# CAN-BUS-Shield-v1_2.net
KiCad netlist of a schematic drawn in EAGLE
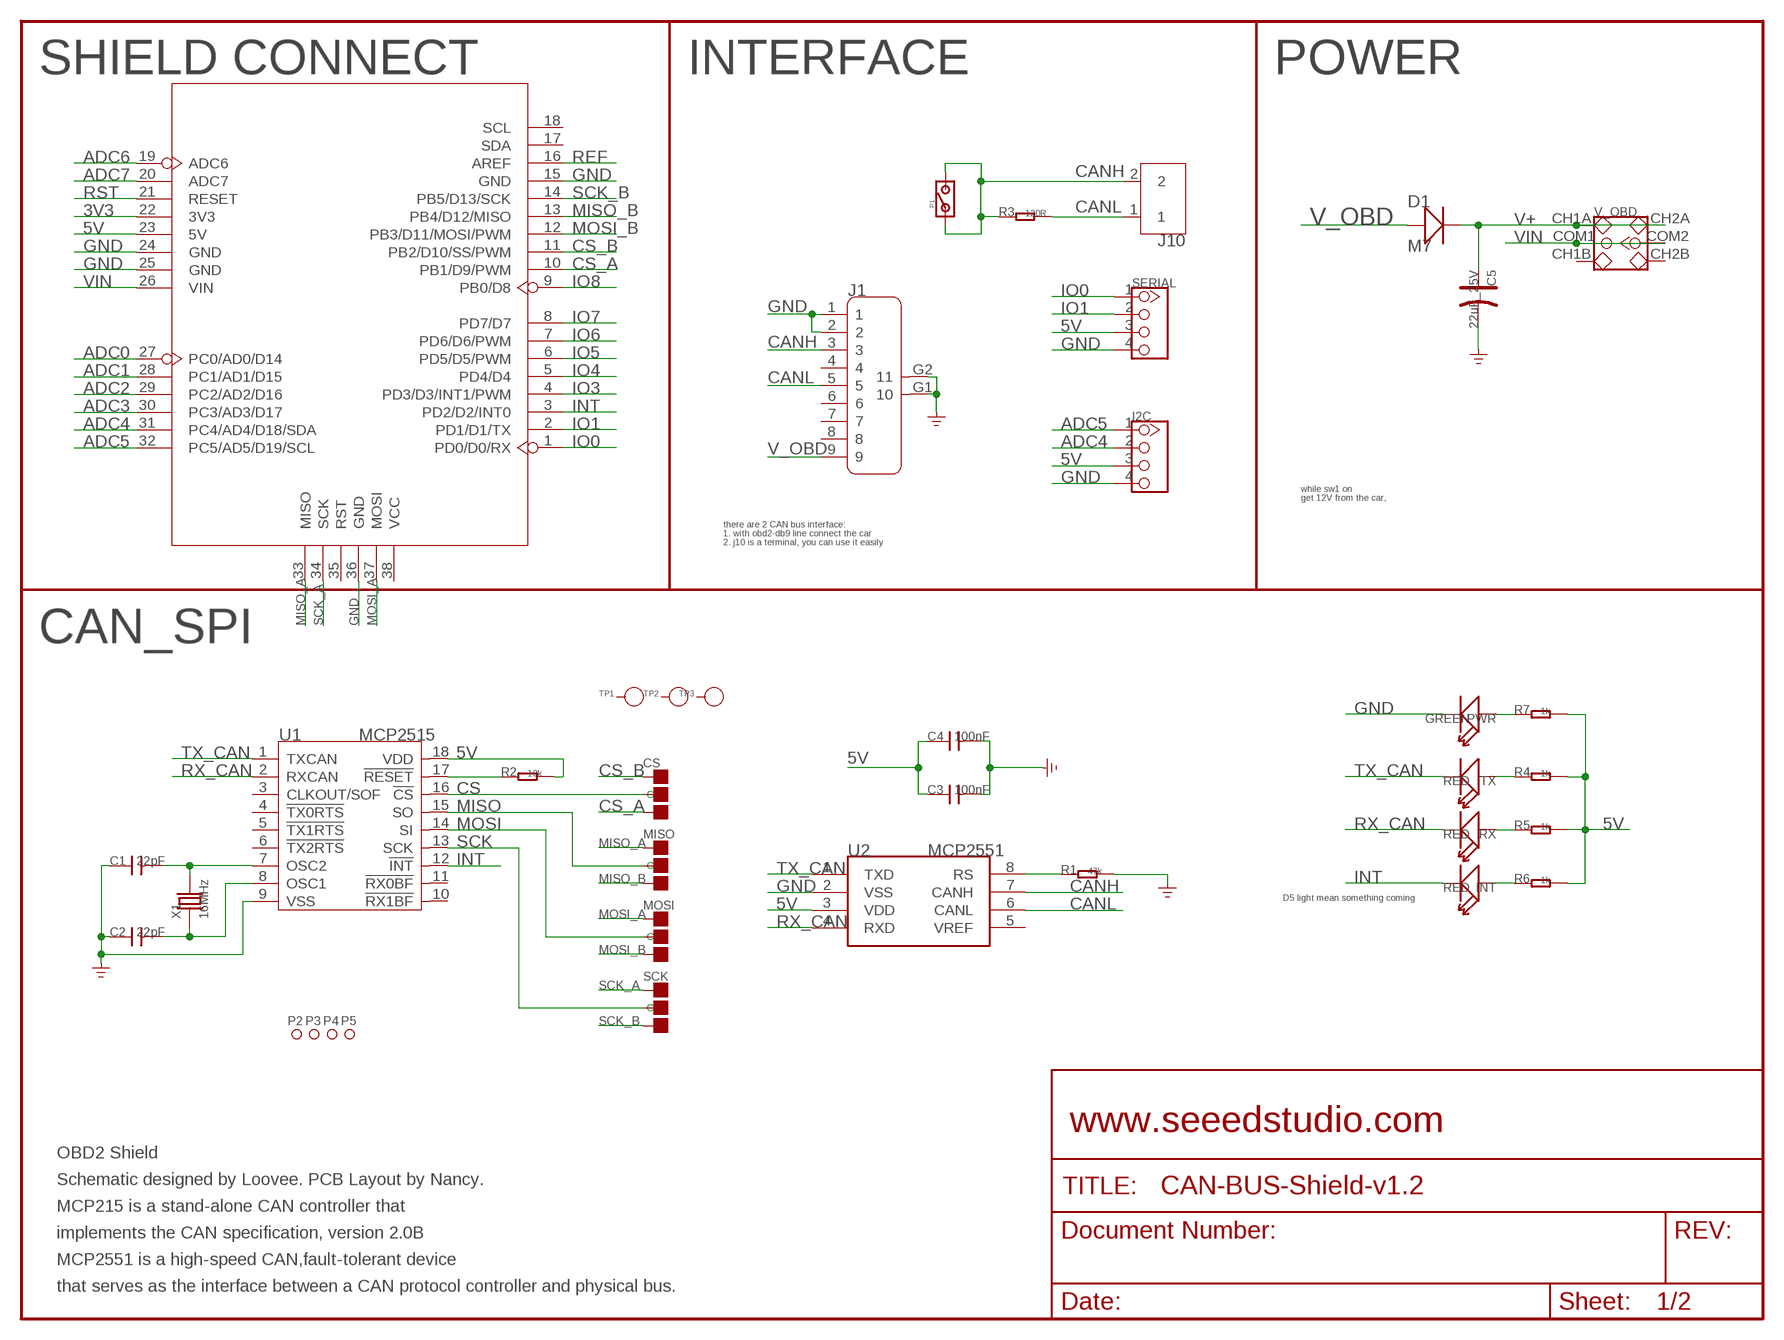
[diagram p0: schematic, sheet 1]

(export (version "E")
  (design (tool "Eeschema 10.0.6"))
  (components
    (comp (ref "C1")
      (value "22pF")
      (footprint "eagle-import:0603")
      (libsource (lib "eagle-import") (part "C-0603"))
    )
    (comp (ref "C2")
      (value "22pF")
      (footprint "eagle-import:0603")
      (libsource (lib "eagle-import") (part "C-0603"))
    )
    (comp (ref "C3")
      (value "100nF")
      (footprint "eagle-import:0603")
      (libsource (lib "eagle-import") (part "C-0603"))
    )
    (comp (ref "C4")
      (value "100nF")
      (footprint "eagle-import:0603")
      (libsource (lib "eagle-import") (part "C-0603"))
    )
    (comp (ref "C5")
      (value "22uF_25V")
      (footprint "eagle-import:ELECTRO-SMD-B-4.8MM")
      (libsource (lib "eagle-import") (part "CAP-ELECTRO-B"))
    )
    (comp (ref "CS")
      (value "PAD-JUMPER-3P-40*40")
      (footprint "eagle-import:3P-SMD-4.1X1.5")
      (libsource (lib "eagle-import") (part "PAD-JUMPER-3P-4040"))
    )
    (comp (ref "D1")
      (value "M7")
      (footprint "eagle-import:D2010")
      (libsource (lib "eagle-import") (part "D-SMA"))
    )
    (comp (ref "I2C")
      (value "TWIG-4P-2.0-2.0")
      (footprint "eagle-import:4P-2.0")
      (libsource (lib "eagle-import") (part "TWIG-4P-2.0-2.0"))
    )
    (comp (ref "INT")
      (value "RED")
      (footprint "eagle-import:LED-0603")
      (libsource (lib "eagle-import") (part "LED'0603'"))
    )
    (comp (ref "J1")
      (value "DB9'MEAL'")
      (footprint "eagle-import:DB9-MEAL")
      (libsource (lib "eagle-import") (part "DB9'MEAL'"))
    )
    (comp (ref "J10")
      (value "SCREW-TERMINAL-2P5.0")
      (footprint "eagle-import:2P-5.0")
      (libsource (lib "eagle-import") (part "SCREW-TERMINAL-2P5.0"))
    )
    (comp (ref "MISO")
      (value "PAD-JUMPER-3P-40*40")
      (footprint "eagle-import:3P-SMD-4.1X1.5")
      (libsource (lib "eagle-import") (part "PAD-JUMPER-3P-4040"))
    )
    (comp (ref "MOSI")
      (value "PAD-JUMPER-3P-40*40")
      (footprint "eagle-import:3P-SMD-4.1X1.5")
      (libsource (lib "eagle-import") (part "PAD-JUMPER-3P-4040"))
    )
    (comp (ref "P1")
      (value "PAD-JUMPER-2P")
      (footprint "eagle-import:2P-SMD-1.78X1.27")
      (libsource (lib "eagle-import") (part "PAD-JUMPER-2P"))
    )
    (comp (ref "P2")
      (value "PAD-MARK'ANNULAR'")
      (footprint "eagle-import:ROUND-MARK-1.0")
      (fields (field (name "PARTNO") "DNP"))
      (libsource (lib "eagle-import") (part "PAD-MARK'ANNULAR'"))
    )
    (comp (ref "P3")
      (value "PAD-MARK'ANNULAR'")
      (footprint "eagle-import:ROUND-MARK-1.0")
      (fields (field (name "PARTNO") "DNP"))
      (libsource (lib "eagle-import") (part "PAD-MARK'ANNULAR'"))
    )
    (comp (ref "P4")
      (value "PAD-MARK'ANNULAR'")
      (footprint "eagle-import:ROUND-MARK-1.0")
      (fields (field (name "PARTNO") "DNP"))
      (libsource (lib "eagle-import") (part "PAD-MARK'ANNULAR'"))
    )
    (comp (ref "P5")
      (value "PAD-MARK'ANNULAR'")
      (footprint "eagle-import:ROUND-MARK-1.0")
      (fields (field (name "PARTNO") "DNP"))
      (libsource (lib "eagle-import") (part "PAD-MARK'ANNULAR'"))
    )
    (comp (ref "PWR")
      (value "GREEN")
      (footprint "eagle-import:LED-0603")
      (libsource (lib "eagle-import") (part "LED'0603'"))
    )
    (comp (ref "R1")
      (value "47k")
      (footprint "eagle-import:0603")
      (libsource (lib "eagle-import") (part "R-0603"))
    )
    (comp (ref "R2")
      (value "10k")
      (footprint "eagle-import:0603")
      (libsource (lib "eagle-import") (part "R-0603"))
    )
    (comp (ref "R3")
      (value "120R")
      (footprint "eagle-import:0603")
      (libsource (lib "eagle-import") (part "R-0603"))
    )
    (comp (ref "R4")
      (value "1k")
      (footprint "eagle-import:0603")
      (libsource (lib "eagle-import") (part "R-0603"))
    )
    (comp (ref "R5")
      (value "1k")
      (footprint "eagle-import:0603")
      (libsource (lib "eagle-import") (part "R-0603"))
    )
    (comp (ref "R6")
      (value "1k")
      (footprint "eagle-import:0603")
      (libsource (lib "eagle-import") (part "R-0603"))
    )
    (comp (ref "R7")
      (value "1k")
      (footprint "eagle-import:0603")
      (libsource (lib "eagle-import") (part "R-0603"))
    )
    (comp (ref "RX")
      (value "RED")
      (footprint "eagle-import:LED-0603")
      (libsource (lib "eagle-import") (part "LED'0603'"))
    )
    (comp (ref "SCK")
      (value "PAD-JUMPER-3P-40*40")
      (footprint "eagle-import:3P-SMD-4.1X1.5")
      (libsource (lib "eagle-import") (part "PAD-JUMPER-3P-4040"))
    )
    (comp (ref "SERIAL")
      (value "TWIG-4P-2.0-2.0")
      (footprint "eagle-import:4P-2.0")
      (libsource (lib "eagle-import") (part "TWIG-4P-2.0-2.0"))
    )
    (comp (ref "TP1")
      (value "PAD-TEST-POINT'4545'")
      (footprint "eagle-import:TP_4545")
      (fields (field (name "PARTNO") "DNP"))
      (libsource (lib "eagle-import") (part "PAD-TEST-POINT'4545'"))
    )
    (comp (ref "TP2")
      (value "PAD-TEST-POINT'4545'")
      (footprint "eagle-import:TP_4545")
      (fields (field (name "PARTNO") "DNP"))
      (libsource (lib "eagle-import") (part "PAD-TEST-POINT'4545'"))
    )
    (comp (ref "TP3")
      (value "PAD-TEST-POINT'4545'")
      (footprint "eagle-import:TP_4545")
      (fields (field (name "PARTNO") "DNP"))
      (libsource (lib "eagle-import") (part "PAD-TEST-POINT'4545'"))
    )
    (comp (ref "TX")
      (value "RED")
      (footprint "eagle-import:LED-0603")
      (libsource (lib "eagle-import") (part "LED'0603'"))
    )
    (comp (ref "U1")
      (value "MCP2515")
      (footprint "eagle-import:SOIC18")
      (libsource (lib "eagle-import") (part "MCP2515-SOIC18"))
    )
    (comp (ref "U2")
      (value "MCP2551")
      (footprint "eagle-import:SOIC8-6.0")
      (libsource (lib "eagle-import") (part "MCP2551-SOIC8"))
    )
    (comp (ref "U4")
      (value "ARDUINO-38P'WITH/-SILK'")
      (footprint "eagle-import:ARDUINO-38P-WITH_-SILK-500519002")
      (libsource (lib "eagle-import") (part "ARDUINO-38P'WITH/-SILK'"))
    )
    (comp (ref "V_OBD")
      (value "SWITCH-2CH-6P")
      (footprint "eagle-import:6P-2CH-2.54-7.6X3.0")
      (libsource (lib "eagle-import") (part "SWITCH-2CH-6P"))
    )
    (comp (ref "X1")
      (value "16MHz")
      (footprint "eagle-import:HC49_S")
      (libsource (lib "eagle-import") (part "CRYSTAL-HC49S"))
    )
  )
  (nets
    (net (code "1") (name "3V3") (class "Default")
      (node (ref "U4") (pin "22") (pinfunction "3V3_22") (pintype "bidirectional"))
    )
    (net (code "2") (name "5V") (class "Default")
      (node (ref "C3") (pin "1") (pinfunction "1_1") (pintype "passive"))
      (node (ref "C4") (pin "1") (pinfunction "1_1") (pintype "passive"))
      (node (ref "I2C") (pin "3") (pinfunction "3_3") (pintype "bidirectional"))
      (node (ref "R2") (pin "2") (pinfunction "2_2") (pintype "passive"))
      (node (ref "R4") (pin "2") (pinfunction "2_2") (pintype "passive"))
      (node (ref "R5") (pin "2") (pinfunction "2_2") (pintype "passive"))
      (node (ref "R6") (pin "2") (pinfunction "2_2") (pintype "passive"))
      (node (ref "R7") (pin "2") (pinfunction "2_2") (pintype "passive"))
      (node (ref "SERIAL") (pin "3") (pinfunction "3_3") (pintype "bidirectional"))
      (node (ref "U1") (pin "18") (pinfunction "VDD_18") (pintype "power_in"))
      (node (ref "U2") (pin "3") (pinfunction "VDD_3") (pintype "bidirectional"))
      (node (ref "U4") (pin "23") (pinfunction "5V_23") (pintype "bidirectional"))
    )
    (net (code "3") (name "ADC0") (class "Default")
      (node (ref "U4") (pin "27") (pinfunction "PC0/AD0/D14_27") (pintype "bidirectional"))
    )
    (net (code "4") (name "ADC1") (class "Default")
      (node (ref "U4") (pin "28") (pinfunction "PC1/AD1/D15_28") (pintype "bidirectional"))
    )
    (net (code "5") (name "ADC2") (class "Default")
      (node (ref "U4") (pin "29") (pinfunction "PC2/AD2/D16_29") (pintype "bidirectional"))
    )
    (net (code "6") (name "ADC3") (class "Default")
      (node (ref "U4") (pin "30") (pinfunction "PC3/AD3/D17_30") (pintype "bidirectional"))
    )
    (net (code "7") (name "ADC4") (class "Default")
      (node (ref "I2C") (pin "2") (pinfunction "2_2") (pintype "bidirectional"))
      (node (ref "U4") (pin "31") (pinfunction "PC4/AD4/D18/SDA_31") (pintype "bidirectional"))
    )
    (net (code "8") (name "ADC5") (class "Default")
      (node (ref "I2C") (pin "1") (pinfunction "1_1") (pintype "bidirectional"))
      (node (ref "U4") (pin "32") (pinfunction "PC5/AD5/D19/SCL_32") (pintype "bidirectional"))
    )
    (net (code "9") (name "ADC6") (class "Default")
      (node (ref "U4") (pin "19") (pinfunction "ADC6_19") (pintype "bidirectional"))
    )
    (net (code "10") (name "ADC7") (class "Default")
      (node (ref "U4") (pin "20") (pinfunction "ADC7_20") (pintype "bidirectional"))
    )
    (net (code "11") (name "CANH") (class "Default")
      (node (ref "J1") (pin "3") (pinfunction "3_3") (pintype "bidirectional"))
      (node (ref "J10") (pin "2") (pinfunction "2_2") (pintype "bidirectional"))
      (node (ref "P1") (pin "1") (pinfunction "1_1") (pintype "bidirectional"))
      (node (ref "P1") (pin "2") (pinfunction "2_2") (pintype "bidirectional"))
      (node (ref "R3") (pin "1") (pinfunction "1_1") (pintype "passive"))
      (node (ref "U2") (pin "7") (pinfunction "CANH_7") (pintype "bidirectional"))
    )
    (net (code "12") (name "CANL") (class "Default")
      (node (ref "J1") (pin "5") (pinfunction "5_5") (pintype "bidirectional"))
      (node (ref "J10") (pin "1") (pinfunction "1_1") (pintype "bidirectional"))
      (node (ref "R3") (pin "2") (pinfunction "2_2") (pintype "passive"))
      (node (ref "U2") (pin "6") (pinfunction "CANL_6") (pintype "bidirectional"))
    )
    (net (code "13") (name "CS") (class "Default")
      (node (ref "CS") (pin "MM") (pinfunction "C_MM") (pintype "bidirectional"))
      (node (ref "U1") (pin "16") (pinfunction "~{CS}_16") (pintype "input"))
    )
    (net (code "14") (name "CS_A") (class "Default")
      (node (ref "CS") (pin "11") (pinfunction "R_11") (pintype "bidirectional"))
      (node (ref "U4") (pin "10") (pinfunction "PB1/D9/PWM_10") (pintype "bidirectional"))
    )
    (net (code "15") (name "CS_B") (class "Default")
      (node (ref "CS") (pin "00") (pinfunction "L_00") (pintype "bidirectional"))
      (node (ref "U4") (pin "11") (pinfunction "PB2/D10/SS/PWM_11") (pintype "bidirectional"))
    )
    (net (code "16") (name "GND") (class "Default")
      (node (ref "C1") (pin "1") (pinfunction "1_1") (pintype "passive"))
      (node (ref "C2") (pin "1") (pinfunction "1_1") (pintype "passive"))
      (node (ref "C3") (pin "2") (pinfunction "2_2") (pintype "passive"))
      (node (ref "C4") (pin "2") (pinfunction "2_2") (pintype "passive"))
      (node (ref "C5") (pin "-") (pinfunction "-_-") (pintype "passive"))
      (node (ref "I2C") (pin "4") (pinfunction "4_4") (pintype "bidirectional"))
      (node (ref "J1") (pin "1") (pinfunction "1_1") (pintype "bidirectional"))
      (node (ref "J1") (pin "2") (pinfunction "2_2") (pintype "bidirectional"))
      (node (ref "J1") (pin "G1") (pinfunction "10_G1") (pintype "bidirectional"))
      (node (ref "J1") (pin "G2") (pinfunction "11_G2") (pintype "bidirectional"))
      (node (ref "PWR") (pin "-") (pinfunction "-_-") (pintype "passive"))
      (node (ref "R1") (pin "2") (pinfunction "2_2") (pintype "passive"))
      (node (ref "SERIAL") (pin "4") (pinfunction "4_4") (pintype "bidirectional"))
      (node (ref "U1") (pin "9") (pinfunction "VSS_9") (pintype "power_in"))
      (node (ref "U2") (pin "2") (pinfunction "VSS_2") (pintype "bidirectional"))
      (node (ref "U4") (pin "15") (pinfunction "GND_15") (pintype "bidirectional"))
      (node (ref "U4") (pin "24") (pinfunction "GND_24") (pintype "bidirectional"))
      (node (ref "U4") (pin "25") (pinfunction "GND_25") (pintype "bidirectional"))
      (node (ref "U4") (pin "36") (pinfunction "GND_36") (pintype "bidirectional"))
    )
    (net (code "17") (name "INT") (class "Default")
      (node (ref "INT") (pin "-") (pinfunction "-_-") (pintype "passive"))
      (node (ref "U1") (pin "12") (pinfunction "~{INT}_12") (pintype "output"))
      (node (ref "U4") (pin "3") (pinfunction "PD2/D2/INT0_3") (pintype "bidirectional"))
    )
    (net (code "18") (name "IO0") (class "Default")
      (node (ref "SERIAL") (pin "1") (pinfunction "1_1") (pintype "bidirectional"))
      (node (ref "U4") (pin "1") (pinfunction "PD0/D0/RX_1") (pintype "bidirectional"))
    )
    (net (code "19") (name "IO1") (class "Default")
      (node (ref "SERIAL") (pin "2") (pinfunction "2_2") (pintype "bidirectional"))
      (node (ref "U4") (pin "2") (pinfunction "PD1/D1/TX_2") (pintype "bidirectional"))
    )
    (net (code "20") (name "IO3") (class "Default")
      (node (ref "U4") (pin "4") (pinfunction "PD3/D3/INT1/PWM_4") (pintype "bidirectional"))
    )
    (net (code "21") (name "IO4") (class "Default")
      (node (ref "U4") (pin "5") (pinfunction "PD4/D4_5") (pintype "bidirectional"))
    )
    (net (code "22") (name "IO5") (class "Default")
      (node (ref "U4") (pin "6") (pinfunction "PD5/D5/PWM_6") (pintype "bidirectional"))
    )
    (net (code "23") (name "IO6") (class "Default")
      (node (ref "U4") (pin "7") (pinfunction "PD6/D6/PWM_7") (pintype "bidirectional"))
    )
    (net (code "24") (name "IO7") (class "Default")
      (node (ref "U4") (pin "8") (pinfunction "PD7/D7_8") (pintype "bidirectional"))
    )
    (net (code "25") (name "IO8") (class "Default")
      (node (ref "U4") (pin "9") (pinfunction "PB0/D8_9") (pintype "bidirectional"))
    )
    (net (code "26") (name "MISO") (class "Default")
      (node (ref "MISO") (pin "MM") (pinfunction "C_MM") (pintype "bidirectional"))
      (node (ref "U1") (pin "15") (pinfunction "SO_15") (pintype "output"))
    )
    (net (code "27") (name "MISO_A") (class "Default")
      (node (ref "MISO") (pin "00") (pinfunction "L_00") (pintype "bidirectional"))
      (node (ref "U4") (pin "33") (pinfunction "MISO_33") (pintype "bidirectional"))
    )
    (net (code "28") (name "MISO_B") (class "Default")
      (node (ref "MISO") (pin "11") (pinfunction "R_11") (pintype "bidirectional"))
      (node (ref "U4") (pin "13") (pinfunction "PB4/D12/MISO_13") (pintype "bidirectional"))
    )
    (net (code "29") (name "MOSI") (class "Default")
      (node (ref "MOSI") (pin "MM") (pinfunction "C_MM") (pintype "bidirectional"))
      (node (ref "U1") (pin "14") (pinfunction "SI_14") (pintype "input"))
    )
    (net (code "30") (name "MOSI_A") (class "Default")
      (node (ref "MOSI") (pin "00") (pinfunction "L_00") (pintype "bidirectional"))
      (node (ref "U4") (pin "37") (pinfunction "MOSI_37") (pintype "bidirectional"))
    )
    (net (code "31") (name "MOSI_B") (class "Default")
      (node (ref "MOSI") (pin "11") (pinfunction "R_11") (pintype "bidirectional"))
      (node (ref "U4") (pin "12") (pinfunction "PB3/D11/MOSI/PWM_12") (pintype "bidirectional"))
    )
    (net (code "32") (name "Net-(INT-Pad+)") (class "Default")
      (node (ref "INT") (pin "+") (pinfunction "+_+") (pintype "passive"))
      (node (ref "R6") (pin "1") (pinfunction "1_1") (pintype "passive"))
    )
    (net (code "33") (name "Net-(PWR-Pad+)") (class "Default")
      (node (ref "PWR") (pin "+") (pinfunction "+_+") (pintype "passive"))
      (node (ref "R7") (pin "1") (pinfunction "1_1") (pintype "passive"))
    )
    (net (code "34") (name "Net-(R4-Pad1)") (class "Default")
      (node (ref "R4") (pin "1") (pinfunction "1_1") (pintype "passive"))
      (node (ref "TX") (pin "+") (pinfunction "+_+") (pintype "passive"))
    )
    (net (code "35") (name "Net-(R5-Pad1)") (class "Default")
      (node (ref "R5") (pin "1") (pinfunction "1_1") (pintype "passive"))
      (node (ref "RX") (pin "+") (pinfunction "+_+") (pintype "passive"))
    )
    (net (code "36") (name "Net-(U1-OSC1)") (class "Default")
      (node (ref "C2") (pin "2") (pinfunction "2_2") (pintype "passive"))
      (node (ref "U1") (pin "8") (pinfunction "OSC1_8") (pintype "input"))
      (node (ref "X1") (pin "1") (pinfunction "1_1") (pintype "passive"))
    )
    (net (code "37") (name "Net-(U1-OSC2)") (class "Default")
      (node (ref "C1") (pin "2") (pinfunction "2_2") (pintype "passive"))
      (node (ref "U1") (pin "7") (pinfunction "OSC2_7") (pintype "output"))
      (node (ref "X1") (pin "2") (pinfunction "2_2") (pintype "passive"))
    )
    (net (code "38") (name "Net-(U1-~{RESET})") (class "Default")
      (node (ref "R2") (pin "1") (pinfunction "1_1") (pintype "passive"))
      (node (ref "U1") (pin "17") (pinfunction "~{RESET}_17") (pintype "input"))
    )
    (net (code "39") (name "Net-(U2-RS)") (class "Default")
      (node (ref "R1") (pin "1") (pinfunction "1_1") (pintype "passive"))
      (node (ref "U2") (pin "8") (pinfunction "RS_8") (pintype "bidirectional"))
    )
    (net (code "40") (name "REF") (class "Default")
      (node (ref "U4") (pin "16") (pinfunction "AREF_16") (pintype "bidirectional"))
    )
    (net (code "41") (name "RST") (class "Default")
      (node (ref "U4") (pin "21") (pinfunction "RESET_21") (pintype "bidirectional"))
    )
    (net (code "42") (name "RX_CAN") (class "Default")
      (node (ref "RX") (pin "-") (pinfunction "-_-") (pintype "passive"))
      (node (ref "U1") (pin "2") (pinfunction "RXCAN_2") (pintype "input"))
      (node (ref "U2") (pin "4") (pinfunction "RXD_4") (pintype "bidirectional"))
    )
    (net (code "43") (name "SCK") (class "Default")
      (node (ref "SCK") (pin "MM") (pinfunction "C_MM") (pintype "bidirectional"))
      (node (ref "U1") (pin "13") (pinfunction "SCK_13") (pintype "input"))
    )
    (net (code "44") (name "SCK_A") (class "Default")
      (node (ref "SCK") (pin "00") (pinfunction "L_00") (pintype "bidirectional"))
      (node (ref "U4") (pin "34") (pinfunction "SCK_34") (pintype "bidirectional"))
    )
    (net (code "45") (name "SCK_B") (class "Default")
      (node (ref "SCK") (pin "11") (pinfunction "R_11") (pintype "bidirectional"))
      (node (ref "U4") (pin "14") (pinfunction "PB5/D13/SCK_14") (pintype "bidirectional"))
    )
    (net (code "46") (name "TX_CAN") (class "Default")
      (node (ref "TX") (pin "-") (pinfunction "-_-") (pintype "passive"))
      (node (ref "U1") (pin "1") (pinfunction "TXCAN_1") (pintype "output"))
      (node (ref "U2") (pin "1") (pinfunction "TXD_1") (pintype "bidirectional"))
    )
    (net (code "47") (name "V+") (class "Default")
      (node (ref "C5") (pin "+") (pinfunction "+_+") (pintype "passive"))
      (node (ref "D1") (pin "-") (pinfunction "-_-") (pintype "passive"))
      (node (ref "V_OBD") (pin "CH1A") (pinfunction "CH1A_CH1A") (pintype "bidirectional"))
      (node (ref "V_OBD") (pin "CH2A") (pinfunction "CH2A_CH2A") (pintype "bidirectional"))
    )
    (net (code "48") (name "VIN") (class "Default")
      (node (ref "U4") (pin "26") (pinfunction "VIN_26") (pintype "bidirectional"))
      (node (ref "V_OBD") (pin "COM1") (pinfunction "COM1_COM1") (pintype "bidirectional"))
      (node (ref "V_OBD") (pin "COM2") (pinfunction "COM2_COM2") (pintype "bidirectional"))
    )
    (net (code "49") (name "V_OBD") (class "Default")
      (node (ref "D1") (pin "+") (pinfunction "+_+") (pintype "passive"))
      (node (ref "J1") (pin "9") (pinfunction "9_9") (pintype "bidirectional"))
    )
    (net (code "50") (name "unconnected-(J1-Pad4)") (class "Default")
      (node (ref "J1") (pin "4") (pinfunction "4_4") (pintype "bidirectional"))
    )
    (net (code "51") (name "unconnected-(J1-Pad6)") (class "Default")
      (node (ref "J1") (pin "6") (pinfunction "6_6") (pintype "bidirectional"))
    )
    (net (code "52") (name "unconnected-(J1-Pad7)") (class "Default")
      (node (ref "J1") (pin "7") (pinfunction "7_7") (pintype "bidirectional"))
    )
    (net (code "53") (name "unconnected-(J1-Pad8)") (class "Default")
      (node (ref "J1") (pin "8") (pinfunction "8_8") (pintype "bidirectional"))
    )
    (net (code "54") (name "unconnected-(TP1-PadT)") (class "Default")
      (node (ref "TP1") (pin "T") (pinfunction "T_T") (pintype "bidirectional"))
    )
    (net (code "55") (name "unconnected-(TP2-PadT)") (class "Default")
      (node (ref "TP2") (pin "T") (pinfunction "T_T") (pintype "bidirectional"))
    )
    (net (code "56") (name "unconnected-(TP3-PadT)") (class "Default")
      (node (ref "TP3") (pin "T") (pinfunction "T_T") (pintype "bidirectional"))
    )
    (net (code "57") (name "unconnected-(U1-CLKOUT{slash}SOF-Pad3)") (class "Default")
      (node (ref "U1") (pin "3") (pinfunction "CLKOUT/SOF_3") (pintype "output"))
    )
    (net (code "58") (name "unconnected-(U1-~{RX0BF}-Pad11)") (class "Default")
      (node (ref "U1") (pin "11") (pinfunction "~{RX0BF}_11") (pintype "output"))
    )
    (net (code "59") (name "unconnected-(U1-~{RX1BF}-Pad10)") (class "Default")
      (node (ref "U1") (pin "10") (pinfunction "~{RX1BF}_10") (pintype "output"))
    )
    (net (code "60") (name "unconnected-(U1-~{TX0RTS}-Pad4)") (class "Default")
      (node (ref "U1") (pin "4") (pinfunction "~{TX0RTS}_4") (pintype "input"))
    )
    (net (code "61") (name "unconnected-(U1-~{TX1RTS}-Pad5)") (class "Default")
      (node (ref "U1") (pin "5") (pinfunction "~{TX1RTS}_5") (pintype "input"))
    )
    (net (code "62") (name "unconnected-(U1-~{TX2RTS}-Pad6)") (class "Default")
      (node (ref "U1") (pin "6") (pinfunction "~{TX2RTS}_6") (pintype "input"))
    )
    (net (code "63") (name "unconnected-(U2-VREF-Pad5)") (class "Default")
      (node (ref "U2") (pin "5") (pinfunction "VREF_5") (pintype "bidirectional"))
    )
    (net (code "64") (name "unconnected-(U4-RST-Pad35)") (class "Default")
      (node (ref "U4") (pin "35") (pinfunction "RST_35") (pintype "bidirectional"))
    )
    (net (code "65") (name "unconnected-(U4-SCL-Pad18)") (class "Default")
      (node (ref "U4") (pin "18") (pinfunction "SCL_18") (pintype "bidirectional"))
    )
    (net (code "66") (name "unconnected-(U4-SDA-Pad17)") (class "Default")
      (node (ref "U4") (pin "17") (pinfunction "SDA_17") (pintype "bidirectional"))
    )
    (net (code "67") (name "unconnected-(U4-VCC-Pad38)") (class "Default")
      (node (ref "U4") (pin "38") (pinfunction "VCC_38") (pintype "bidirectional"))
    )
    (net (code "68") (name "unconnected-(V_OBD-PadCH1B)") (class "Default")
      (node (ref "V_OBD") (pin "CH1B") (pinfunction "CH1B_CH1B") (pintype "bidirectional"))
    )
    (net (code "69") (name "unconnected-(V_OBD-PadCH2B)") (class "Default")
      (node (ref "V_OBD") (pin "CH2B") (pinfunction "CH2B_CH2B") (pintype "bidirectional"))
    )
  )
)
